# ADC_Reference.net
KiCad netlist of a schematic drawn in Altium Designer
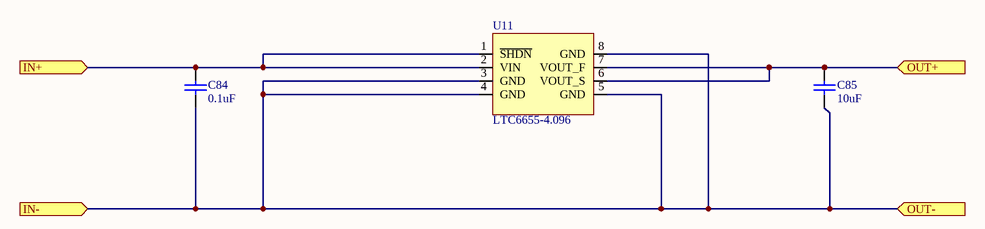
[diagram p0: ADC_Reference.SchDoc]

(export (version "E")
  (design (tool "Eeschema 10.0.6"))
  (components
    (comp (ref "C84")
      (value "0.1uF")
      (footprint "0402_Cap")
      (description "Capacitor, 0.1uF, 0805")
      (libsource (lib "Arturo_Approved") (part "CL21B104KACNNNC"))
    )
    (comp (ref "C85")
      (value "10uF")
      (footprint "0402_Cap")
      (description "Capacitor, 10uF, 0805")
      (libsource (lib "Arturo_Approved") (part "CL21A106KAFN3NE"))
    )
    (comp (ref "U11")
      (value "LTC6655-4.096")
      (footprint "MSOP_8")
      (description "Voltage Reference 4.096V")
      (libsource (lib "Arturo_Approved") (part "LTC6655CHMS8-4.096#PBF"))
    )
  )
  (nets
    (net (code "1") (name "/IN+") (class "Default")
      (node (ref "C84") (pin "2") (pinfunction "2_2") (pintype "passive"))
      (node (ref "U11") (pin "1") (pinfunction "~{SHDN}_1") (pintype "passive"))
      (node (ref "U11") (pin "2") (pinfunction "VIN_2") (pintype "passive"))
    )
    (net (code "2") (name "/IN-") (class "Default")
      (node (ref "C84") (pin "1") (pinfunction "1_1") (pintype "passive"))
      (node (ref "C85") (pin "1") (pinfunction "1_1") (pintype "passive"))
      (node (ref "U11") (pin "3") (pinfunction "GND_3") (pintype "passive"))
      (node (ref "U11") (pin "4") (pinfunction "GND_4") (pintype "passive"))
      (node (ref "U11") (pin "5") (pinfunction "GND_5") (pintype "passive"))
      (node (ref "U11") (pin "8") (pinfunction "GND_8") (pintype "passive"))
    )
    (net (code "3") (name "/OUT+") (class "Default")
      (node (ref "C85") (pin "2") (pinfunction "2_2") (pintype "passive"))
      (node (ref "U11") (pin "6") (pinfunction "VOUT_S_6") (pintype "passive"))
      (node (ref "U11") (pin "7") (pinfunction "VOUT_F_7") (pintype "passive"))
    )
  )
)
